# openSX70-dongle-USB-V1-1.net
KiCad netlist of a schematic drawn in EAGLE
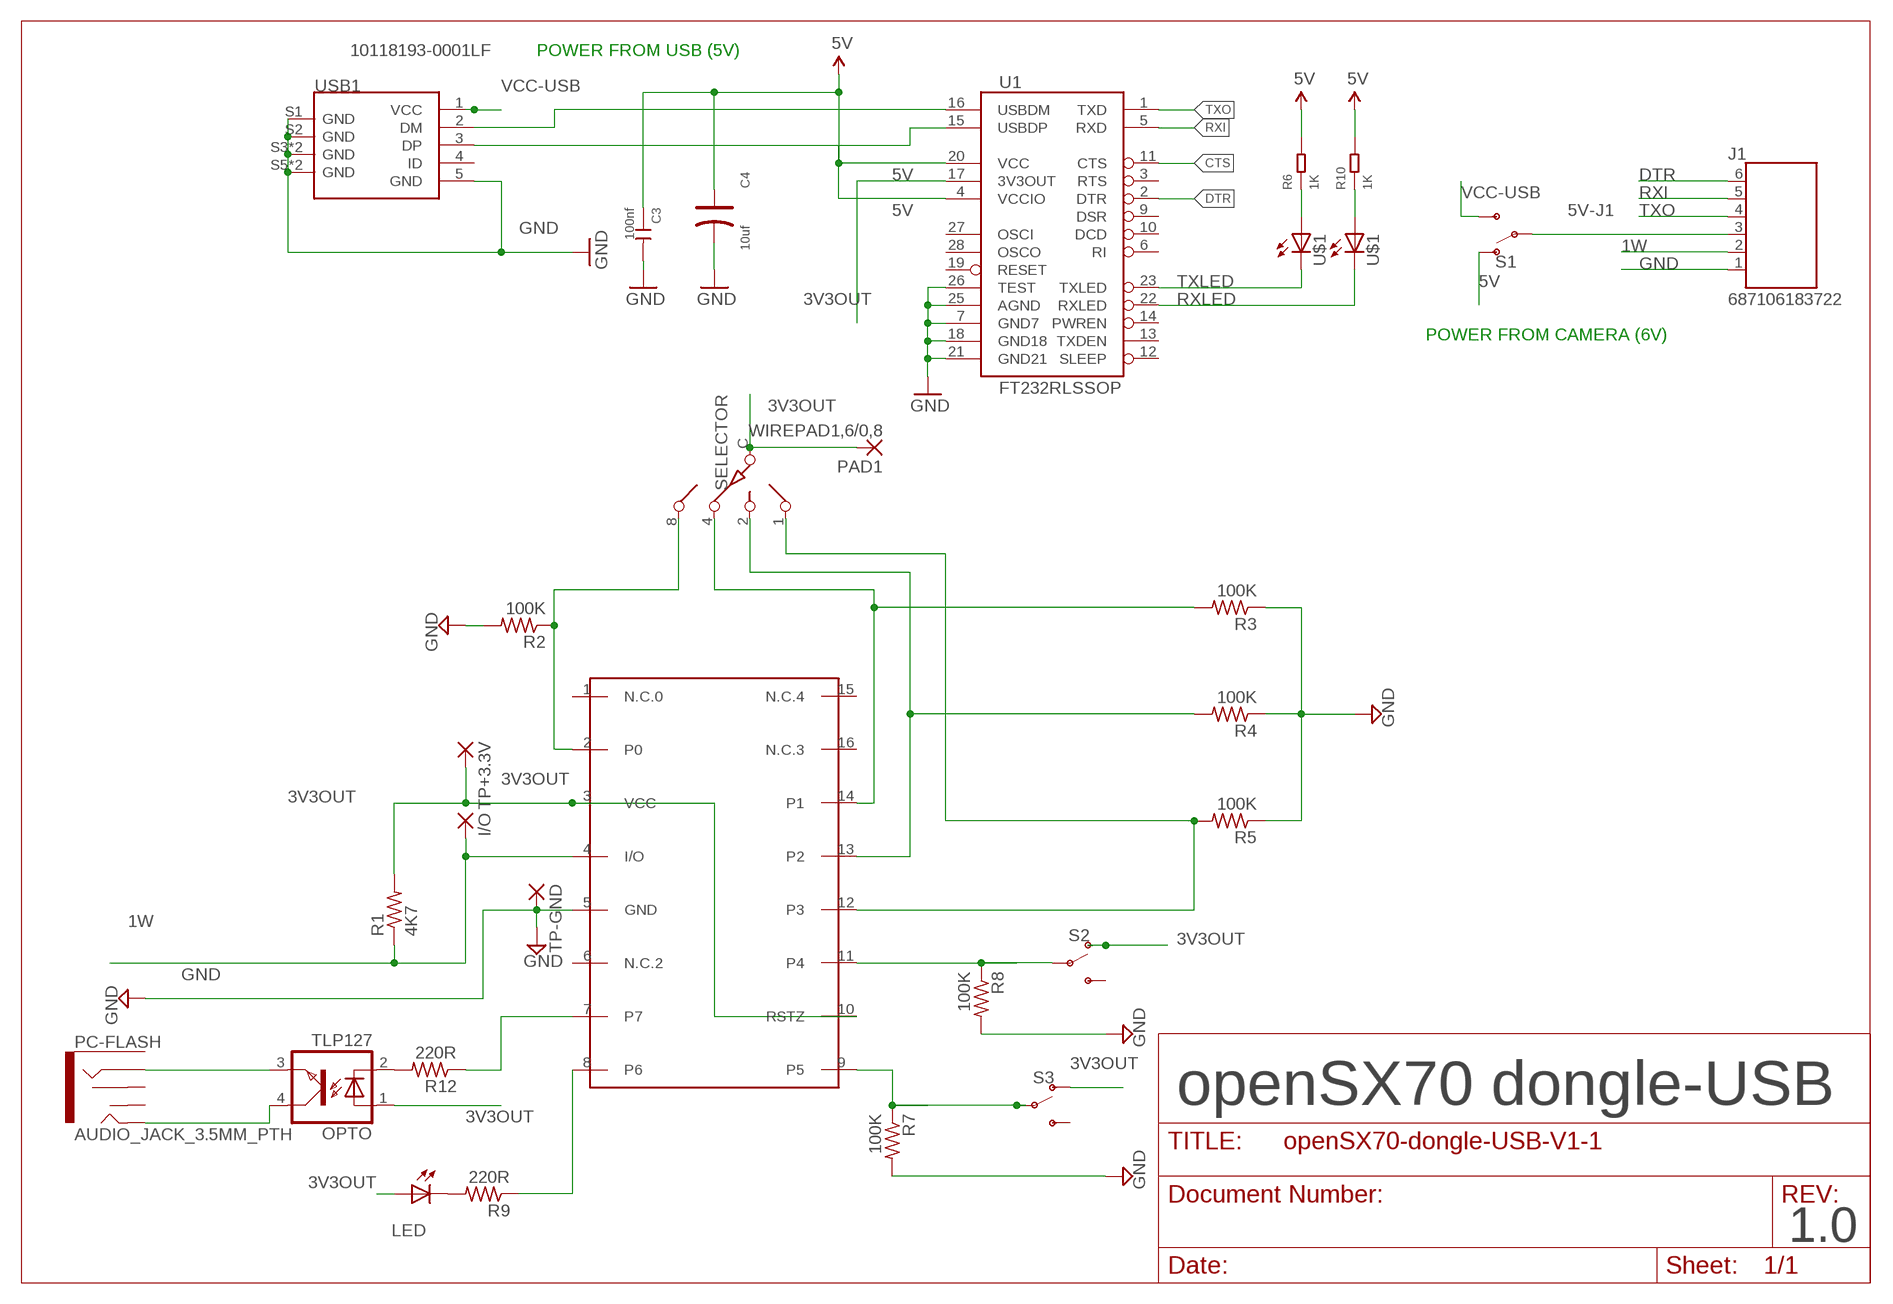
[diagram p0: schematic, sheet 1]

(export (version "E")
  (design (tool "Eeschema 10.0.6"))
  (components
    (comp (ref "C3")
      (value "100nf")
      (footprint "eagle-import:C0603")
      (fields (field (name "MPN") "CC0603KRX7R9BB104"))
      (libsource (lib "eagle-import") (part "CERAMIC-100NF-50V-10%-X7R(0603)"))
    )
    (comp (ref "C4")
      (value "10uf")
      (footprint "eagle-import:AVX-A")
      (fields (field (name "MPN") "TAJA106K016RNJ"))
      (libsource (lib "eagle-import") (part "TANTALUM-SMD-10UF-16V-10%(AVX-A)"))
    )
    (comp (ref "DS2408")
      (value "DS2408")
      (footprint "eagle-import:SO16")
      (libsource (lib "eagle-import") (part "DS2408"))
    )
    (comp (ref "I/O")
      (value "SMD2")
      (footprint "eagle-import:SMD1,27-2,54")
      (libsource (lib "eagle-import") (part "SMD2"))
    )
    (comp (ref "J1")
      (value "687106183722")
      (footprint "eagle-import:687106183722")
      (fields (field (name "MF") "Wurth Electronics"))
      (libsource (lib "eagle-import") (part "687106183722"))
    )
    (comp (ref "LED")
      (value "LED3MM")
      (footprint "eagle-import:LED3MM")
      (libsource (lib "eagle-import") (part "LED3MM"))
    )
    (comp (ref "OPTO")
      (value "TLP127")
      (footprint "eagle-import:SO-4")
      (libsource (lib "eagle-import") (part "TLP127"))
    )
    (comp (ref "PAD1")
      (value "WIREPAD1,6/0,8")
      (footprint "eagle-import:1,6_0,8")
      (libsource (lib "eagle-import") (part "WIREPAD1,6/0,8"))
    )
    (comp (ref "PC-FLASH")
      (value "AUDIO_JACK_3.5MM_PTH")
      (footprint "eagle-import:AUDIO-JACK")
      (libsource (lib "eagle-import") (part "AUDIO_JACK_3.5MM_PTH"))
    )
    (comp (ref "R1")
      (value "4K7")
      (footprint "eagle-import:M0805")
      (libsource (lib "eagle-import") (part "R-US_M0805"))
    )
    (comp (ref "R2")
      (value "100K")
      (footprint "eagle-import:M0805")
      (libsource (lib "eagle-import") (part "R-US_M0805"))
    )
    (comp (ref "R3")
      (value "100K")
      (footprint "eagle-import:M0805")
      (libsource (lib "eagle-import") (part "R-US_M0805"))
    )
    (comp (ref "R4")
      (value "100K")
      (footprint "eagle-import:M0805")
      (libsource (lib "eagle-import") (part "R-US_M0805"))
    )
    (comp (ref "R5")
      (value "100K")
      (footprint "eagle-import:M0805")
      (libsource (lib "eagle-import") (part "R-US_M0805"))
    )
    (comp (ref "R6")
      (value "1K")
      (footprint "eagle-import:R0603")
      (fields (field (name "MPN") "RC0603FR-071KL"))
      (libsource (lib "eagle-import") (part "SMD-RES-1K-1%-1/10W(0603)"))
    )
    (comp (ref "R7")
      (value "100K")
      (footprint "eagle-import:M0805")
      (libsource (lib "eagle-import") (part "R-US_M0805"))
    )
    (comp (ref "R8")
      (value "100K")
      (footprint "eagle-import:M0805")
      (libsource (lib "eagle-import") (part "R-US_M0805"))
    )
    (comp (ref "R9")
      (value "220R")
      (footprint "eagle-import:M0805")
      (libsource (lib "eagle-import") (part "R-US_M0805"))
    )
    (comp (ref "R10")
      (value "1K")
      (footprint "eagle-import:R0603")
      (fields (field (name "MPN") "RC0603FR-071KL"))
      (libsource (lib "eagle-import") (part "SMD-RES-1K-1%-1/10W(0603)"))
    )
    (comp (ref "R12")
      (value "220R")
      (footprint "eagle-import:M0805")
      (libsource (lib "eagle-import") (part "R-US_M0805"))
    )
    (comp (ref "S1")
      (value "SWITCH-SPDT-SMD-RIGHT-ANGLE")
      (footprint "eagle-import:SWITCH_SPST_SMD_A")
      (libsource (lib "eagle-import") (part "SWITCH-SPDT-SMD-RIGHT-ANGLE"))
    )
    (comp (ref "S2")
      (value "SWITCH-SPDT-SMD-RIGHT-ANGLE")
      (footprint "eagle-import:SWITCH_SPST_SMD_A")
      (libsource (lib "eagle-import") (part "SWITCH-SPDT-SMD-RIGHT-ANGLE"))
    )
    (comp (ref "S3")
      (value "SWITCH-SPDT-SMD-RIGHT-ANGLE")
      (footprint "eagle-import:SWITCH_SPST_SMD_A")
      (libsource (lib "eagle-import") (part "SWITCH-SPDT-SMD-RIGHT-ANGLE"))
    )
    (comp (ref "SELECTOR")
      (value "SW-C16")
      (footprint "eagle-import:SW-C16")
      (libsource (lib "eagle-import") (part "SW-C16"))
    )
    (comp (ref "TP+3.3V")
      (value "SMD2")
      (footprint "eagle-import:SMD1,27-2,54")
      (libsource (lib "eagle-import") (part "SMD2"))
    )
    (comp (ref "TP-GND")
      (value "SMD2")
      (footprint "eagle-import:SMD1,27-2,54")
      (libsource (lib "eagle-import") (part "SMD2"))
    )
    (comp (ref "U$1")
      (value "DUAL-LED-0603-BIS")
      (footprint "eagle-import:LED_APHB1608SYKSURKC")
      (libsource (lib "eagle-import") (part "DUAL-LED-0603-BIS"))
    )
    (comp (ref "U1")
      (value "FT232RLSSOP")
      (footprint "eagle-import:SSOP28DB")
      (libsource (lib "eagle-import") (part "FT232RLSSOP"))
    )
    (comp (ref "USB1")
      (value "10118193-0001LF")
      (footprint "eagle-import:MICRO-USB5+6P-SMD-0.65-B")
      (libsource (lib "eagle-import") (part "MICRO-USB-SMD-B-(10118193-0001LF)"))
    )
  )
  (nets
    (net (code "1") (name "/1W") (class "Default")
      (node (ref "DS2408") (pin "4") (pinfunction "I/O_4") (pintype "bidirectional"))
      (node (ref "I/O") (pin "1") (pinfunction "P_1") (pintype "passive"))
      (node (ref "J1") (pin "2") (pinfunction "5_2") (pintype "passive"))
      (node (ref "R1") (pin "1") (pinfunction "1_1") (pintype "passive"))
    )
    (net (code "2") (name "/3V3OUT") (class "Default")
      (node (ref "DS2408") (pin "10") (pinfunction "RSTZ_10") (pintype "bidirectional"))
      (node (ref "DS2408") (pin "3") (pinfunction "VCC_3") (pintype "bidirectional"))
      (node (ref "LED") (pin "A") (pinfunction "A_A") (pintype "passive"))
      (node (ref "OPTO") (pin "1") (pinfunction "A_1") (pintype "passive"))
      (node (ref "PAD1") (pin "1") (pinfunction "P_1") (pintype "passive"))
      (node (ref "R1") (pin "2") (pinfunction "2_2") (pintype "passive"))
      (node (ref "S2") (pin "1") (pinfunction "O_1") (pintype "passive"))
      (node (ref "S3") (pin "1") (pinfunction "O_1") (pintype "passive"))
      (node (ref "SELECTOR") (pin "C") (pinfunction "C_C") (pintype "passive"))
      (node (ref "TP+3.3V") (pin "1") (pinfunction "P_1") (pintype "passive"))
      (node (ref "U1") (pin "17") (pinfunction "3V3OUT_17") (pintype "output"))
    )
    (net (code "3") (name "/5V-J1") (class "Default")
      (node (ref "J1") (pin "3") (pinfunction "4_3") (pintype "passive"))
      (node (ref "S1") (pin "2") (pinfunction "P_2") (pintype "passive"))
    )
    (net (code "4") (name "/RXLED") (class "Default")
      (node (ref "U$1") (pin "4") (pinfunction "C1_4") (pintype "passive"))
      (node (ref "U1") (pin "22") (pinfunction "RXLED_22") (pintype "input"))
    )
    (net (code "5") (name "/TXLED") (class "Default")
      (node (ref "U$1") (pin "2") (pinfunction "C_2") (pintype "passive"))
      (node (ref "U1") (pin "23") (pinfunction "TXLED_23") (pintype "input"))
    )
    (net (code "6") (name "/VCC-USB") (class "Default")
      (node (ref "S1") (pin "3") (pinfunction "S_3") (pintype "passive"))
      (node (ref "USB1") (pin "1") (pinfunction "VCC_1") (pintype "bidirectional"))
    )
    (net (code "7") (name "5V") (class "Default")
      (node (ref "C3") (pin "1") (pinfunction "1_1") (pintype "passive"))
      (node (ref "C4") (pin "+") (pinfunction "+_+") (pintype "passive"))
      (node (ref "R10") (pin "2") (pinfunction "2_2") (pintype "passive"))
      (node (ref "R6") (pin "2") (pinfunction "2_2") (pintype "passive"))
      (node (ref "S1") (pin "1") (pinfunction "O_1") (pintype "passive"))
      (node (ref "U1") (pin "20") (pinfunction "VCC_20") (pintype "power_in"))
      (node (ref "U1") (pin "4") (pinfunction "VCCIO_4") (pintype "power_in"))
    )
    (net (code "8") (name "CTS") (class "Default")
      (node (ref "U1") (pin "11") (pinfunction "CTS_11") (pintype "input"))
    )
    (net (code "9") (name "DTR") (class "Default")
      (node (ref "J1") (pin "6") (pinfunction "1_6") (pintype "passive"))
      (node (ref "U1") (pin "2") (pinfunction "DTR_2") (pintype "output"))
    )
    (net (code "10") (name "GND") (class "Default")
      (node (ref "C3") (pin "2") (pinfunction "2_2") (pintype "passive"))
      (node (ref "C4") (pin "-") (pinfunction "-_-") (pintype "passive"))
      (node (ref "DS2408") (pin "5") (pinfunction "GND_5") (pintype "bidirectional"))
      (node (ref "J1") (pin "1") (pinfunction "6_1") (pintype "passive"))
      (node (ref "R2") (pin "2") (pinfunction "2_2") (pintype "passive"))
      (node (ref "R3") (pin "1") (pinfunction "1_1") (pintype "passive"))
      (node (ref "R4") (pin "1") (pinfunction "1_1") (pintype "passive"))
      (node (ref "R5") (pin "1") (pinfunction "1_1") (pintype "passive"))
      (node (ref "R7") (pin "2") (pinfunction "2_2") (pintype "passive"))
      (node (ref "R8") (pin "2") (pinfunction "2_2") (pintype "passive"))
      (node (ref "TP-GND") (pin "1") (pinfunction "P_1") (pintype "passive"))
      (node (ref "U1") (pin "18") (pinfunction "GND18_18") (pintype "power_in"))
      (node (ref "U1") (pin "21") (pinfunction "GND21_21") (pintype "power_in"))
      (node (ref "U1") (pin "25") (pinfunction "AGND_25") (pintype "power_in"))
      (node (ref "U1") (pin "26") (pinfunction "TEST_26") (pintype "input"))
      (node (ref "U1") (pin "7") (pinfunction "GND7_7") (pintype "power_in"))
      (node (ref "USB1") (pin "5") (pinfunction "GND_5") (pintype "bidirectional"))
      (node (ref "USB1") (pin "S1") (pinfunction "GND_S1") (pintype "bidirectional"))
      (node (ref "USB1") (pin "S2") (pinfunction "GND_S2") (pintype "bidirectional"))
      (node (ref "USB1") (pin "S3") (pinfunction "GND_S3") (pintype "bidirectional"))
      (node (ref "USB1") (pin "S4") (pinfunction "GND_S4") (pintype "bidirectional"))
      (node (ref "USB1") (pin "S5") (pinfunction "GND_S5") (pintype "bidirectional"))
      (node (ref "USB1") (pin "S6") (pinfunction "GND_S6") (pintype "bidirectional"))
    )
    (net (code "11") (name "Net-(DS2408-P0)") (class "Default")
      (node (ref "DS2408") (pin "2") (pinfunction "P0_2") (pintype "bidirectional"))
      (node (ref "R2") (pin "1") (pinfunction "1_1") (pintype "passive"))
      (node (ref "SELECTOR") (pin "8") (pinfunction "8_8") (pintype "passive"))
    )
    (net (code "12") (name "Net-(DS2408-P1)") (class "Default")
      (node (ref "DS2408") (pin "14") (pinfunction "P1_14") (pintype "bidirectional"))
      (node (ref "R3") (pin "2") (pinfunction "2_2") (pintype "passive"))
      (node (ref "SELECTOR") (pin "4") (pinfunction "4_4") (pintype "passive"))
    )
    (net (code "13") (name "Net-(DS2408-P2)") (class "Default")
      (node (ref "DS2408") (pin "13") (pinfunction "P2_13") (pintype "bidirectional"))
      (node (ref "R4") (pin "2") (pinfunction "2_2") (pintype "passive"))
      (node (ref "SELECTOR") (pin "2") (pinfunction "2_2") (pintype "passive"))
    )
    (net (code "14") (name "Net-(DS2408-P3)") (class "Default")
      (node (ref "DS2408") (pin "12") (pinfunction "P3_12") (pintype "bidirectional"))
      (node (ref "R5") (pin "2") (pinfunction "2_2") (pintype "passive"))
      (node (ref "SELECTOR") (pin "1") (pinfunction "1_1") (pintype "passive"))
    )
    (net (code "15") (name "Net-(DS2408-P4)") (class "Default")
      (node (ref "DS2408") (pin "11") (pinfunction "P4_11") (pintype "bidirectional"))
      (node (ref "R8") (pin "1") (pinfunction "1_1") (pintype "passive"))
      (node (ref "S2") (pin "2") (pinfunction "P_2") (pintype "passive"))
    )
    (net (code "16") (name "Net-(DS2408-P5)") (class "Default")
      (node (ref "DS2408") (pin "9") (pinfunction "P5_9") (pintype "bidirectional"))
      (node (ref "R7") (pin "1") (pinfunction "1_1") (pintype "passive"))
      (node (ref "S3") (pin "2") (pinfunction "P_2") (pintype "passive"))
    )
    (net (code "17") (name "Net-(DS2408-P6)") (class "Default")
      (node (ref "DS2408") (pin "8") (pinfunction "P6_8") (pintype "bidirectional"))
      (node (ref "R9") (pin "1") (pinfunction "1_1") (pintype "passive"))
    )
    (net (code "18") (name "Net-(DS2408-P7)") (class "Default")
      (node (ref "DS2408") (pin "7") (pinfunction "P7_7") (pintype "bidirectional"))
      (node (ref "R12") (pin "1") (pinfunction "1_1") (pintype "passive"))
    )
    (net (code "19") (name "Net-(LED-C)") (class "Default")
      (node (ref "LED") (pin "K") (pinfunction "C_K") (pintype "passive"))
      (node (ref "R9") (pin "2") (pinfunction "2_2") (pintype "passive"))
    )
    (net (code "20") (name "Net-(OPTO-C)") (class "Default")
      (node (ref "OPTO") (pin "2") (pinfunction "C_2") (pintype "passive"))
      (node (ref "R12") (pin "2") (pinfunction "2_2") (pintype "passive"))
    )
    (net (code "21") (name "Net-(OPTO-COL)") (class "Default")
      (node (ref "OPTO") (pin "4") (pinfunction "COL_4") (pintype "passive"))
      (node (ref "PC-FLASH") (pin "TIP") (pinfunction "TIP_TIP") (pintype "bidirectional"))
    )
    (net (code "22") (name "Net-(OPTO-EMIT)") (class "Default")
      (node (ref "OPTO") (pin "3") (pinfunction "EMIT_3") (pintype "passive"))
      (node (ref "PC-FLASH") (pin "RING") (pinfunction "RING_RING") (pintype "bidirectional"))
    )
    (net (code "23") (name "Net-(U$1-A)") (class "Default")
      (node (ref "R6") (pin "1") (pinfunction "1_1") (pintype "passive"))
      (node (ref "U$1") (pin "1") (pinfunction "A_1") (pintype "passive"))
    )
    (net (code "24") (name "Net-(U$1-A1)") (class "Default")
      (node (ref "R10") (pin "1") (pinfunction "1_1") (pintype "passive"))
      (node (ref "U$1") (pin "3") (pinfunction "A1_3") (pintype "passive"))
    )
    (net (code "25") (name "Net-(U1-USBDM)") (class "Default")
      (node (ref "U1") (pin "16") (pinfunction "USBDM_16") (pintype "bidirectional"))
      (node (ref "USB1") (pin "2") (pinfunction "DM_2") (pintype "bidirectional"))
    )
    (net (code "26") (name "Net-(U1-USBDP)") (class "Default")
      (node (ref "U1") (pin "15") (pinfunction "USBDP_15") (pintype "bidirectional"))
      (node (ref "USB1") (pin "3") (pinfunction "DP_3") (pintype "bidirectional"))
    )
    (net (code "27") (name "RXI") (class "Default")
      (node (ref "J1") (pin "5") (pinfunction "2_5") (pintype "passive"))
      (node (ref "U1") (pin "5") (pinfunction "RXD_5") (pintype "input"))
    )
    (net (code "28") (name "TXO") (class "Default")
      (node (ref "J1") (pin "4") (pinfunction "3_4") (pintype "passive"))
      (node (ref "U1") (pin "1") (pinfunction "TXD_1") (pintype "output"))
    )
    (net (code "29") (name "unconnected-(DS2408-N.C.0-Pad1)") (class "Default")
      (node (ref "DS2408") (pin "1") (pinfunction "N.C.0_1") (pintype "bidirectional"))
    )
    (net (code "30") (name "unconnected-(DS2408-N.C.2-Pad6)") (class "Default")
      (node (ref "DS2408") (pin "6") (pinfunction "N.C.2_6") (pintype "bidirectional"))
    )
    (net (code "31") (name "unconnected-(DS2408-N.C.3-Pad16)") (class "Default")
      (node (ref "DS2408") (pin "16") (pinfunction "N.C.3_16") (pintype "bidirectional"))
    )
    (net (code "32") (name "unconnected-(DS2408-N.C.4-Pad15)") (class "Default")
      (node (ref "DS2408") (pin "15") (pinfunction "N.C.4_15") (pintype "bidirectional"))
    )
    (net (code "33") (name "unconnected-(PC-FLASH-PadRSH)") (class "Default")
      (node (ref "PC-FLASH") (pin "RSH") (pinfunction "RSH_RSH") (pintype "bidirectional"))
    )
    (net (code "34") (name "unconnected-(PC-FLASH-PadSLEEVE)") (class "Default")
      (node (ref "PC-FLASH") (pin "SLEEVE") (pinfunction "SLEEVE_SLEEVE") (pintype "bidirectional"))
    )
    (net (code "35") (name "unconnected-(PC-FLASH-PadTSH)") (class "Default")
      (node (ref "PC-FLASH") (pin "TSH") (pinfunction "TSH_TSH") (pintype "bidirectional"))
    )
    (net (code "36") (name "unconnected-(S2-S-Pad3)") (class "Default")
      (node (ref "S2") (pin "3") (pinfunction "S_3") (pintype "passive"))
    )
    (net (code "37") (name "unconnected-(S3-S-Pad3)") (class "Default")
      (node (ref "S3") (pin "3") (pinfunction "S_3") (pintype "passive"))
    )
    (net (code "38") (name "unconnected-(U1-DCD-Pad10)") (class "Default")
      (node (ref "U1") (pin "10") (pinfunction "DCD_10") (pintype "input"))
    )
    (net (code "39") (name "unconnected-(U1-DSR-Pad9)") (class "Default")
      (node (ref "U1") (pin "9") (pinfunction "DSR_9") (pintype "input"))
    )
    (net (code "40") (name "unconnected-(U1-OSCI-Pad27)") (class "Default")
      (node (ref "U1") (pin "27") (pinfunction "OSCI_27") (pintype "input"))
    )
    (net (code "41") (name "unconnected-(U1-OSCO-Pad28)") (class "Default")
      (node (ref "U1") (pin "28") (pinfunction "OSCO_28") (pintype "output"))
    )
    (net (code "42") (name "unconnected-(U1-PWREN-Pad14)") (class "Default")
      (node (ref "U1") (pin "14") (pinfunction "PWREN_14") (pintype "input"))
    )
    (net (code "43") (name "unconnected-(U1-RESET-Pad19)") (class "Default")
      (node (ref "U1") (pin "19") (pinfunction "RESET_19") (pintype "input"))
    )
    (net (code "44") (name "unconnected-(U1-RI-Pad6)") (class "Default")
      (node (ref "U1") (pin "6") (pinfunction "RI_6") (pintype "input"))
    )
    (net (code "45") (name "unconnected-(U1-RTS-Pad3)") (class "Default")
      (node (ref "U1") (pin "3") (pinfunction "RTS_3") (pintype "output"))
    )
    (net (code "46") (name "unconnected-(U1-SLEEP-Pad12)") (class "Default")
      (node (ref "U1") (pin "12") (pinfunction "SLEEP_12") (pintype "input"))
    )
    (net (code "47") (name "unconnected-(U1-TXDEN-Pad13)") (class "Default")
      (node (ref "U1") (pin "13") (pinfunction "TXDEN_13") (pintype "input"))
    )
    (net (code "48") (name "unconnected-(USB1-ID-Pad4)") (class "Default")
      (node (ref "USB1") (pin "4") (pinfunction "ID_4") (pintype "bidirectional"))
    )
  )
)
